# CurrentSense.net
KiCad netlist of a schematic drawn in Altium Designer
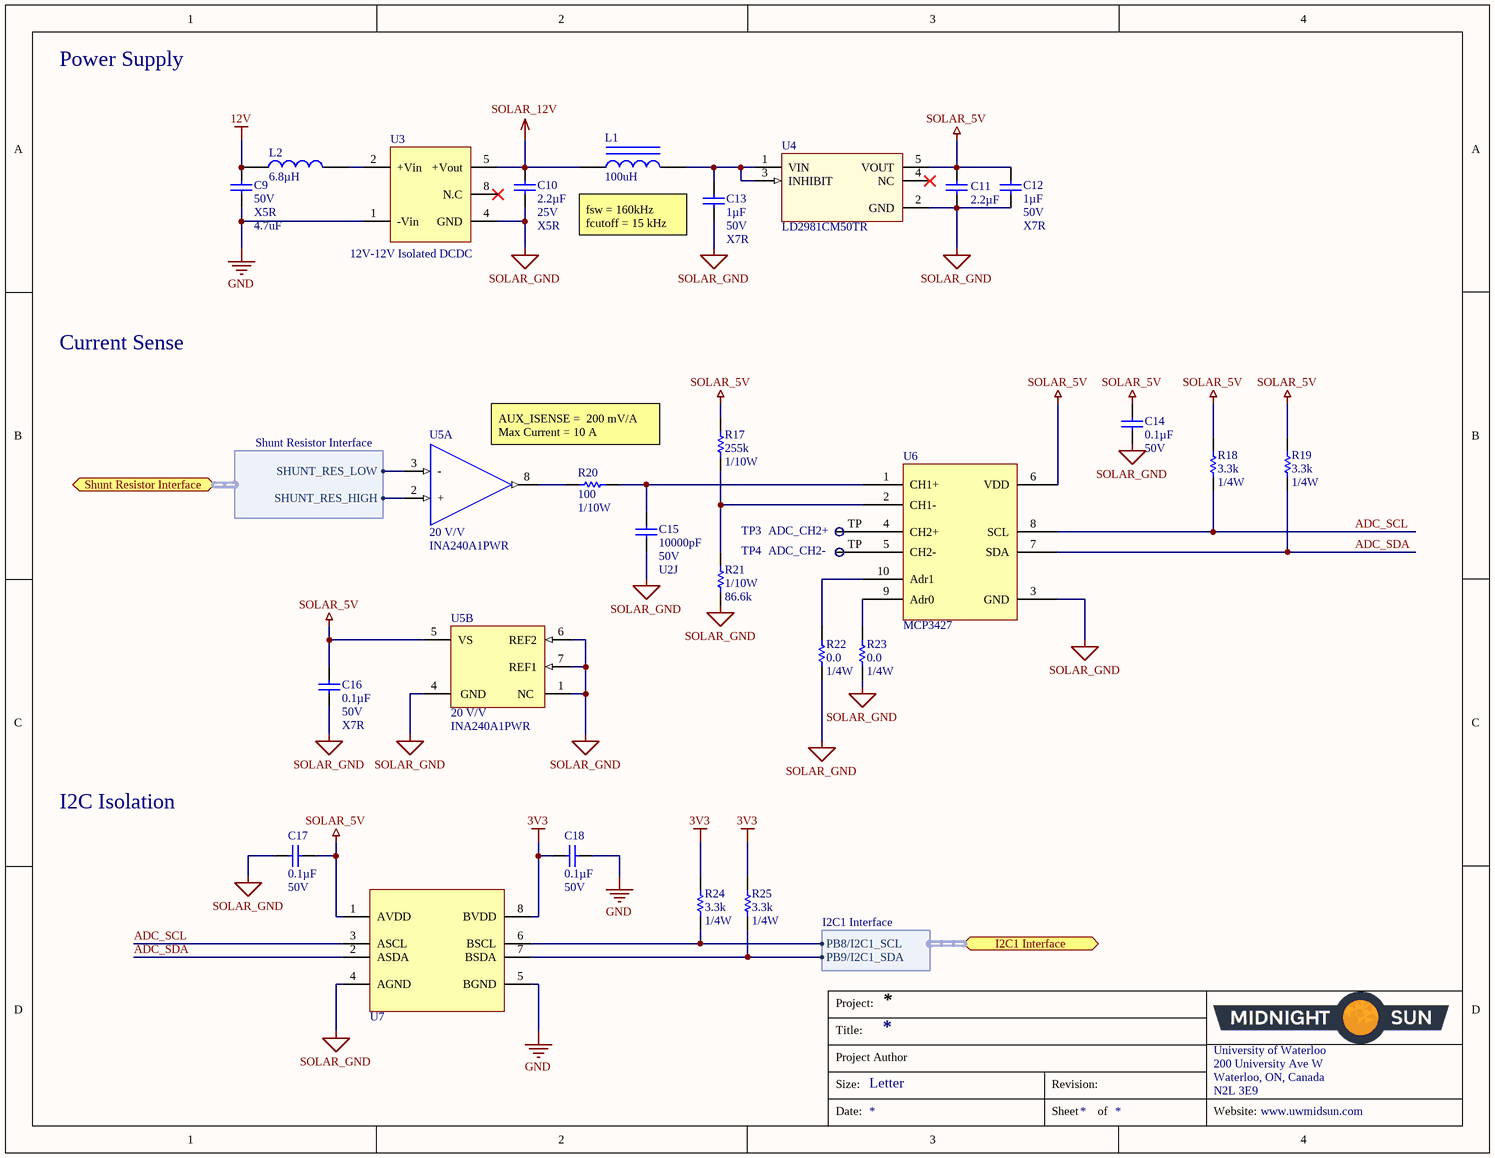
[diagram p0: CurrentSense.SchDoc]

(export (version "E")
  (design (tool "Eeschema 10.0.6"))
  (components
    (comp (ref "C9")
      (value "4.7uF")
      (footprint "CAP, 0805")
      (description "4.7µF ±20% 50V Ceramic Capacitor X5R 0805 (2012 Metric)")
      (fields
        (field (name "TOLERANCE") "±20%")
        (field (name "VOLTAGE - RATED") "50V")
        (field (name "TEMPERATURE COEFFICIENT") "X5R")
        (field (name "Comment") "CAP CER 4.7UF 50V 10% X5R 0805")
      )
      (libsource (lib "Schematic Diagrams") (part "CAP CER 4.7UF 50V 10% X5R 0805"))
    )
    (comp (ref "C10")
      (value "CAP CER 2.2UF 25V 10% X5R 0603")
      (footprint "CAP, 0603")
      (description "2.2µF ±10% 25V Ceramic Capacitor X5R 0603 (1608 Metric)")
      (fields
        (field (name "TOLERANCE") "±10%")
        (field (name "CAPACITANCE") "2.2µF")
        (field (name "VOLTAGE") "25V")
        (field (name "TEMPERATURE COEFFICIENT") "X5R")
      )
      (libsource (lib "Schematic Diagrams") (part "CAP CER 2.2UF 25V 10% X5R 0603"))
    )
    (comp (ref "C11")
      (value "CAP CER 2.2UF 25V 10% X5R 0603")
      (footprint "CAP, 0603")
      (description "2.2µF ±10% 25V Ceramic Capacitor X5R 0603 (1608 Metric)")
      (fields
        (field (name "TOLERANCE") "±10%")
        (field (name "CAPACITANCE") "2.2µF")
        (field (name "VOLTAGE") "25V")
      )
      (libsource (lib "Schematic Diagrams") (part "CAP CER 2.2UF 25V 10% X5R 0603"))
    )
    (comp (ref "C12")
      (value "CAP CER 1UF 50V 10% X7R 0603")
      (footprint "CAP, 0603")
      (description "1µF ±10% 50V Ceramic Capacitor X7R 0603 (1608 Metric)")
      (fields
        (field (name "TOLERANCE") "±10%")
        (field (name "CAPACITANCE") "1µF")
        (field (name "VOLTAGE") "50V")
        (field (name "TEMPERATURE COEFFICIENT") "X7R")
      )
      (libsource (lib "Schematic Diagrams") (part "CAP CER 1UF 50V 10% X7R 0603"))
    )
    (comp (ref "C13")
      (value "CAP CER 1UF 50V 10% X7R 0603")
      (footprint "CAP, 0603")
      (description "1µF ±10% 50V Ceramic Capacitor X7R 0603 (1608 Metric)")
      (fields
        (field (name "TOLERANCE") "±10%")
        (field (name "CAPACITANCE") "1µF")
        (field (name "VOLTAGE") "50V")
        (field (name "TEMPERATURE COEFFICIENT") "X7R")
      )
      (libsource (lib "Schematic Diagrams") (part "CAP CER 1UF 50V 10% X7R 0603"))
    )
    (comp (ref "C14")
      (value "CAP CER 0.1UF 50V 10% X7R 0603")
      (footprint "CAP, 0603")
      (description "0.10µF ±10% 50V Ceramic Capacitor X7R 0603 (1608 Metric)")
      (fields
        (field (name "TOLERANCE") "±10%")
        (field (name "CAPACITANCE") "0.1µF")
        (field (name "VOLTAGE") "50V")
      )
      (libsource (lib "Schematic Diagrams") (part "CAP CER 0.1UF 50V 10% X7R 0603"))
    )
    (comp (ref "C15")
      (value "CAP CER 10nF 50V 5% X7R 0603")
      (footprint "CAP, 0603")
      (description "10000pF ±5% 50V Ceramic Capacitor U2J 0603 (1608 Metric)")
      (fields
        (field (name "TOLERANCE") "±5%")
        (field (name "CAPACITANCE") "10000pF")
        (field (name "VOLTAGE") "50V")
        (field (name "TEMPERATURE COEFFICIENT") "U2J")
      )
      (libsource (lib "Schematic Diagrams") (part "CAP CER 10nF 50V 5% X7R 0603"))
    )
    (comp (ref "C16")
      (value "CAP CER 0.1UF 50V 10% X7R 0603")
      (footprint "CAP, 0603")
      (description "0.10µF ±10% 50V Ceramic Capacitor X7R 0603 (1608 Metric)")
      (fields
        (field (name "TOLERANCE") "±10%")
        (field (name "CAPACITANCE") "0.1µF")
        (field (name "VOLTAGE") "50V")
        (field (name "TEMPERATURE COEFFICIENT") "X7R")
      )
      (libsource (lib "Schematic Diagrams") (part "CAP CER 0.1UF 50V 10% X7R 0603"))
    )
    (comp (ref "C17")
      (value "CAP CER 0.1UF 50V 10% X7R 0603")
      (footprint "CAP, 0603")
      (description "0.10µF ±10% 50V Ceramic Capacitor X7R 0603 (1608 Metric)")
      (fields
        (field (name "TOLERANCE") "±10%")
        (field (name "CAPACITANCE") "0.1µF")
        (field (name "VOLTAGE") "50V")
      )
      (libsource (lib "Schematic Diagrams") (part "CAP CER 0.1UF 50V 10% X7R 0603"))
    )
    (comp (ref "C18")
      (value "CAP CER 0.1UF 50V 10% X7R 0603")
      (footprint "CAP, 0603")
      (description "0.10µF ±10% 50V Ceramic Capacitor X7R 0603 (1608 Metric)")
      (fields
        (field (name "TOLERANCE") "±10%")
        (field (name "CAPACITANCE") "0.1µF")
        (field (name "VOLTAGE") "50V")
      )
      (libsource (lib "Schematic Diagrams") (part "CAP CER 0.1UF 50V 10% X7R 0603"))
    )
    (comp (ref "L1")
      (value "100uH")
      (footprint "1210")
      (description "100µH Unshielded Wirewound Inductor 60mA 11 Ohm Max 1210 (3225 Metric)")
      (fields
        (field (name "MANUFACTURER") "EPCOS (TDK)")
        (field (name "MANUFACTURER PART NUMBER") "B82422T1104J000")
      )
      (libsource (lib "Schematic Diagrams") (part "IND 100uH 60mA 5% 1210"))
    )
    (comp (ref "L2")
      (value "IND 6.8uH 260mA 20% 1210")
      (footprint "NLFV32T-6R8M-EF/IND 6.8uH")
      (description "6.8µH Shielded Wirewound Inductor 260mA 204 mOhm Max 1210 (3225 Metric)")
      (fields (field (name "TOLERANCE") "±20%") (field (name "INDUCTANCE") "6.8µH"))
      (libsource (lib "Schematic Diagrams") (part "IND 6.8uH 260mA 20% 1210"))
    )
    (comp (ref "R17")
      (value "RES 255K OHM 1% 1/10W 0603")
      (footprint "RES, 0603")
      (description "255k Ohm ±1% 0.1W, 1/10W Chip Resistor 0603 (1608 Metric) Moisture Resistant Thick Film")
      (fields
        (field (name "TOLERANCE") "±1%")
        (field (name "RESISTANCE (OHMS)") "255k")
        (field (name "POWER (WATTS)") "1/10W")
      )
      (libsource (lib "Schematic Diagrams") (part "RES 255K OHM 1% 1/10W 0603"))
    )
    (comp (ref "R18")
      (value "RES 3.3K OHM 1% 1/4W 0603")
      (footprint "RES, 0603")
      (fields
        (field (name "TOLERANCE") "±1%")
        (field (name "RESISTANCE") "3.3k")
        (field (name "POWER") "1/4W")
      )
      (libsource (lib "Schematic Diagrams") (part "RES 3.3K OHM 1% 1/4W 0603"))
    )
    (comp (ref "R19")
      (value "RES 3.3K OHM 1% 1/4W 0603")
      (footprint "RES, 0603")
      (fields
        (field (name "TOLERANCE") "±1%")
        (field (name "RESISTANCE") "3.3k")
        (field (name "POWER") "1/4W")
      )
      (libsource (lib "Schematic Diagrams") (part "RES 3.3K OHM 1% 1/4W 0603"))
    )
    (comp (ref "R20")
      (value "RES 100 OHM 1% 1/10W 0603")
      (footprint "RES, 0603")
      (description "100 Ohm ±1% 0.1W, 1/10W Chip Resistor 0603 (1608 Metric) Moisture Resistant Thick Film")
      (fields
        (field (name "TOLERANCE") "±1%")
        (field (name "RESISTANCE") "100")
        (field (name "POWER") "1/10W")
      )
      (libsource (lib "Schematic Diagrams") (part "RES 100 OHM 1% 1/10W 0603"))
    )
    (comp (ref "R21")
      (value "RES 86.6K OHM 1% 1/10W 0603")
      (footprint "RES, 0603")
      (description "86.6k Ohm ±1% 0.1W, 1/10W Chip Resistor 0603 (1608 Metric) Automotive AEC-Q200 Thick Film")
      (fields
        (field (name "MANUFACTURER") "Panasonic Electronic Components")
        (field (name "MANUFACTURER PART NUMBER") "ERJ-3EKF8662V")
        (field (name "POWER (WATTS)") "1/10W")
        (field (name "RESISTANCE (OHMS)") "86.6k")
      )
      (libsource (lib "Schematic Diagrams") (part "RES 86.6K OHM 1% 1/10W 0603"))
    )
    (comp (ref "R22")
      (value "RES 0.0 OHM 1/4W 0603")
      (footprint "RES, 0603")
      (description "RES SMD 0.0 OHM JUMPER 1/4W 0603")
      (fields (field (name "RESISTANCE") "0.0") (field (name "POWER (WATTS)") "1/4W"))
      (libsource (lib "Schematic Diagrams") (part "RES 0.0 OHM 1/4W 0603"))
    )
    (comp (ref "R23")
      (value "RES 0.0 OHM 1/4W 0603")
      (footprint "RES, 0603")
      (description "RES SMD 0.0 OHM JUMPER 1/4W 0603")
      (fields (field (name "RESISTANCE") "0.0") (field (name "POWER (WATTS)") "1/4W"))
      (libsource (lib "Schematic Diagrams") (part "RES 0.0 OHM 1/4W 0603"))
    )
    (comp (ref "R24")
      (value "RES 3.3K OHM 1% 1/4W 0603")
      (footprint "RES, 0603")
      (fields
        (field (name "TOLERANCE") "±1%")
        (field (name "RESISTANCE") "3.3k")
        (field (name "POWER") "1/4W")
      )
      (libsource (lib "Schematic Diagrams") (part "RES 3.3K OHM 1% 1/4W 0603"))
    )
    (comp (ref "R25")
      (value "RES 3.3K OHM 1% 1/4W 0603")
      (footprint "RES, 0603")
      (fields
        (field (name "TOLERANCE") "±1%")
        (field (name "RESISTANCE") "3.3k")
        (field (name "POWER") "1/4W")
      )
      (libsource (lib "Schematic Diagrams") (part "RES 3.3K OHM 1% 1/4W 0603"))
    )
    (comp (ref "TP3")
      (value "ADC_CH2+")
      (footprint "Test Point")
      (libsource (lib "Schematic Diagrams") (part "Test Point"))
    )
    (comp (ref "TP4")
      (value "ADC_CH2-")
      (footprint "Test Point")
      (libsource (lib "Schematic Diagrams") (part "Test Point"))
    )
    (comp (ref "U3")
      (value "IC DCDC ISOLATED 12V 1W 8-SMD 5-LEAD")
      (footprint "IC, Isolated DCDC")
      (description "Isolated Module DC DC Converter 1 Output 12V 84mA 10.8V - 13.2V Input")
      (fields (field (name "POWER") "1W") (field (name "TYPE") "12V-12V Isolated DCDC"))
      (libsource (lib "Schematic Diagrams") (part "IC DCDC ISOLATED 12V 1W 8-SMD 5-LEAD"))
    )
    (comp (ref "U4")
      (value "IC REG LDO 5V 0.1A SOT23-5")
      (footprint "SOT95P280X145-5N")
      (description "Linear Voltage Regulator IC Positive Fixed Output 5V 100mA SOT-23-5")
      (fields (field (name "MANUFACTURER PART NUMBER 1") "LD2981CM50TR"))
      (libsource (lib "Schematic Diagrams") (part "IC REG LDO 5V 0.1A SOT23-5"))
    )
    (comp (ref "U5")
      (value "20 V/V")
      (footprint "IC CURRENT AMPLIFIER INA240 TSSOP-8")
      (description "Current Sense Amplifier 1 Circuit 8-TSSOP")
      (fields (field (name "MANUFACTURER PART NUMBER 1") "INA240A1PWR"))
      (libsource (lib "Schematic Diagrams") (part "IC CURRENT AMPLIFIER INA240A1 20V/V 8-TSSOP"))
    )
    (comp (ref "U6")
      (value "IC ADC MCP3427 10MSOP")
      (footprint "IC ADC MCP3427")
      (description "16 Bit Analog to Digital Converter 2 Input 1 Sigma-Delta 10-MSOP")
      (fields
        (field (name "MANUFACTURER") "Microchip Technology")
        (field (name "MANUFACTURER PART NUMBER") "MCP3427-E/UN")
        (field (name "BASE PART NUMBER") "MCP3427")
      )
      (libsource (lib "Schematic Diagrams") (part "IC ADC MCP3427 10MSOP"))
    )
    (comp (ref "U7")
      (value "IC DGTL ISO I2C 3.75KV 2CH 8SOIC")
      (footprint "IC DGTL ISO 3.75KV I2C 8SOIC NARROW BODY")
      (description "I²C Digital Isolator 3750Vrms 2 Channel 35kV/µs CMTI 8-SOIC (0.154\", 3.90mm Width)")
      (libsource (lib "Schematic Diagrams") (part "IC DGTL ISO I2C 3.75KV 2CH 8SOIC"))
    )
  )
  (nets
    (net (code "5") (name "/ADC_SCL") (class "Default")
      (node (ref "R18") (pin "2") (pinfunction "2_2") (pintype "passive"))
      (node (ref "U6") (pin "8") (pinfunction "SCL_8") (pintype "passive"))
      (node (ref "U7") (pin "3") (pinfunction "ASCL_3") (pintype "open_collector"))
    )
    (net (code "6") (name "/ADC_SDA") (class "Default")
      (node (ref "R19") (pin "2") (pinfunction "2_2") (pintype "passive"))
      (node (ref "U6") (pin "7") (pinfunction "SDA_7") (pintype "passive"))
      (node (ref "U7") (pin "2") (pinfunction "ASDA_2") (pintype "open_collector"))
    )
    (net (code "7") (name "/PB8{slash}I2C1_SCL") (class "Default")
      (node (ref "R24") (pin "2") (pinfunction "2_2") (pintype "passive"))
      (node (ref "U7") (pin "6") (pinfunction "BSCL_6") (pintype "passive"))
    )
    (net (code "8") (name "/PB9{slash}I2C1_SDA") (class "Default")
      (node (ref "R25") (pin "2") (pinfunction "2_2") (pintype "passive"))
      (node (ref "U7") (pin "7") (pinfunction "BSDA_7") (pintype "passive"))
    )
    (net (code "9") (name "/SHUNT_RES_HIGH") (class "Default")
      (node (ref "U5") (pin "2") (pinfunction "+_2") (pintype "input"))
    )
    (net (code "10") (name "/SHUNT_RES_LOW") (class "Default")
      (node (ref "U5") (pin "3") (pinfunction "-_3") (pintype "input"))
    )
    (net (code "13") (name "3V3") (class "Default")
      (node (ref "C18") (pin "1") (pinfunction "1_1") (pintype "passive"))
      (node (ref "R24") (pin "1") (pinfunction "1_1") (pintype "passive"))
      (node (ref "R25") (pin "1") (pinfunction "1_1") (pintype "passive"))
      (node (ref "U7") (pin "8") (pinfunction "BVDD_8") (pintype "passive"))
    )
    (net (code "14") (name "12V") (class "Default")
      (node (ref "C9") (pin "1") (pinfunction "1_1") (pintype "passive"))
      (node (ref "L2") (pin "1") (pinfunction "1_1") (pintype "passive"))
    )
    (net (code "15") (name "GND") (class "Default")
      (node (ref "C18") (pin "2") (pinfunction "2_2") (pintype "passive"))
      (node (ref "C9") (pin "2") (pinfunction "2_2") (pintype "passive"))
      (node (ref "U3") (pin "1") (pinfunction "-Vin_1") (pintype "passive"))
      (node (ref "U7") (pin "5") (pinfunction "BGND_5") (pintype "passive"))
    )
    (net (code "16") (name "Net-(TP3-1)") (class "Default")
      (node (ref "TP3") (pin "TP") (pinfunction "1_TP") (pintype "passive"))
      (node (ref "U6") (pin "4") (pinfunction "CH2+_4") (pintype "passive"))
    )
    (net (code "17") (name "Net-(TP4-1)") (class "Default")
      (node (ref "TP4") (pin "TP") (pinfunction "1_TP") (pintype "passive"))
      (node (ref "U6") (pin "5") (pinfunction "CH2-_5") (pintype "passive"))
    )
    (net (code "18") (name "Net-(U3-+Vin)") (class "Default")
      (node (ref "L2") (pin "2") (pinfunction "2_2") (pintype "passive"))
      (node (ref "U3") (pin "2") (pinfunction "+Vin_2") (pintype "passive"))
    )
    (net (code "19") (name "Net-(U4-INHIBIT)") (class "Default")
      (node (ref "C13") (pin "1") (pinfunction "1_1") (pintype "passive"))
      (node (ref "L1") (pin "2") (pinfunction "2_2") (pintype "passive"))
      (node (ref "U4") (pin "1") (pinfunction "VIN_1") (pintype "power_in"))
      (node (ref "U4") (pin "3") (pinfunction "INHIBIT_3") (pintype "input"))
    )
    (net (code "20") (name "Net-(U5A-OUTPUT)") (class "Default")
      (node (ref "R20") (pin "1") (pinfunction "1_1") (pintype "passive"))
      (node (ref "U5") (pin "8") (pinfunction "OUTPUT_8") (pintype "output"))
    )
    (net (code "21") (name "Net-(U6-Adr0)") (class "Default")
      (node (ref "R23") (pin "1") (pinfunction "1_1") (pintype "passive"))
      (node (ref "U6") (pin "9") (pinfunction "Adr0_9") (pintype "passive"))
    )
    (net (code "22") (name "Net-(U6-Adr1)") (class "Default")
      (node (ref "R22") (pin "1") (pinfunction "1_1") (pintype "passive"))
      (node (ref "U6") (pin "10") (pinfunction "Adr1_10") (pintype "passive"))
    )
    (net (code "23") (name "Net-(U6-CH1+)") (class "Default")
      (node (ref "C15") (pin "1") (pinfunction "1_1") (pintype "passive"))
      (node (ref "R20") (pin "2") (pinfunction "2_2") (pintype "passive"))
      (node (ref "U6") (pin "1") (pinfunction "CH1+_1") (pintype "passive"))
    )
    (net (code "24") (name "Net-(U6-CH1-)") (class "Default")
      (node (ref "R17") (pin "2") (pinfunction "2_2") (pintype "passive"))
      (node (ref "R21") (pin "1") (pinfunction "1_1") (pintype "passive"))
      (node (ref "U6") (pin "2") (pinfunction "CH1-_2") (pintype "passive"))
    )
    (net (code "25") (name "SOLAR_5V") (class "Default")
      (node (ref "C11") (pin "1") (pinfunction "1_1") (pintype "passive"))
      (node (ref "C12") (pin "1") (pinfunction "1_1") (pintype "passive"))
      (node (ref "C14") (pin "1") (pinfunction "1_1") (pintype "passive"))
      (node (ref "C16") (pin "1") (pinfunction "1_1") (pintype "passive"))
      (node (ref "C17") (pin "2") (pinfunction "2_2") (pintype "passive"))
      (node (ref "R17") (pin "1") (pinfunction "1_1") (pintype "passive"))
      (node (ref "R18") (pin "1") (pinfunction "1_1") (pintype "passive"))
      (node (ref "R19") (pin "1") (pinfunction "1_1") (pintype "passive"))
      (node (ref "U4") (pin "5") (pinfunction "VOUT_5") (pintype "power_in"))
      (node (ref "U5") (pin "5") (pinfunction "VS_5") (pintype "power_in"))
      (node (ref "U6") (pin "6") (pinfunction "VDD_6") (pintype "passive"))
      (node (ref "U7") (pin "1") (pinfunction "AVDD_1") (pintype "passive"))
    )
    (net (code "26") (name "SOLAR_12V") (class "Default")
      (node (ref "C10") (pin "1") (pinfunction "1_1") (pintype "passive"))
      (node (ref "L1") (pin "1") (pinfunction "1_1") (pintype "passive"))
      (node (ref "U3") (pin "5") (pinfunction "+Vout_5") (pintype "passive"))
    )
    (net (code "27") (name "SOLAR_GND") (class "Default")
      (node (ref "C10") (pin "2") (pinfunction "2_2") (pintype "passive"))
      (node (ref "C11") (pin "2") (pinfunction "2_2") (pintype "passive"))
      (node (ref "C12") (pin "2") (pinfunction "2_2") (pintype "passive"))
      (node (ref "C13") (pin "2") (pinfunction "2_2") (pintype "passive"))
      (node (ref "C14") (pin "2") (pinfunction "2_2") (pintype "passive"))
      (node (ref "C15") (pin "2") (pinfunction "2_2") (pintype "passive"))
      (node (ref "C16") (pin "2") (pinfunction "2_2") (pintype "passive"))
      (node (ref "C17") (pin "1") (pinfunction "1_1") (pintype "passive"))
      (node (ref "R21") (pin "2") (pinfunction "2_2") (pintype "passive"))
      (node (ref "R22") (pin "2") (pinfunction "2_2") (pintype "passive"))
      (node (ref "R23") (pin "2") (pinfunction "2_2") (pintype "passive"))
      (node (ref "U3") (pin "4") (pinfunction "GND_4") (pintype "passive"))
      (node (ref "U4") (pin "2") (pinfunction "GND_2") (pintype "power_in"))
      (node (ref "U5") (pin "1") (pinfunction "NC_1") (pintype "power_in"))
      (node (ref "U5") (pin "4") (pinfunction "GND_4") (pintype "power_in"))
      (node (ref "U5") (pin "6") (pinfunction "REF2_6") (pintype "input"))
      (node (ref "U5") (pin "7") (pinfunction "REF1_7") (pintype "input"))
      (node (ref "U6") (pin "3") (pinfunction "GND_3") (pintype "passive"))
      (node (ref "U7") (pin "4") (pinfunction "AGND_4") (pintype "passive"))
    )
    (net (code "28") (name "unconnected-(U3-N.C-Pad8)") (class "Default")
      (node (ref "U3") (pin "8") (pinfunction "N.C_8") (pintype "passive+no_connect"))
    )
    (net (code "29") (name "unconnected-(U4-NC-Pad4)") (class "Default")
      (node (ref "U4") (pin "4") (pinfunction "NC_4") (pintype "passive+no_connect"))
    )
  )
)
